# DAQ.net
KiCad netlist of a schematic drawn in Altium Designer
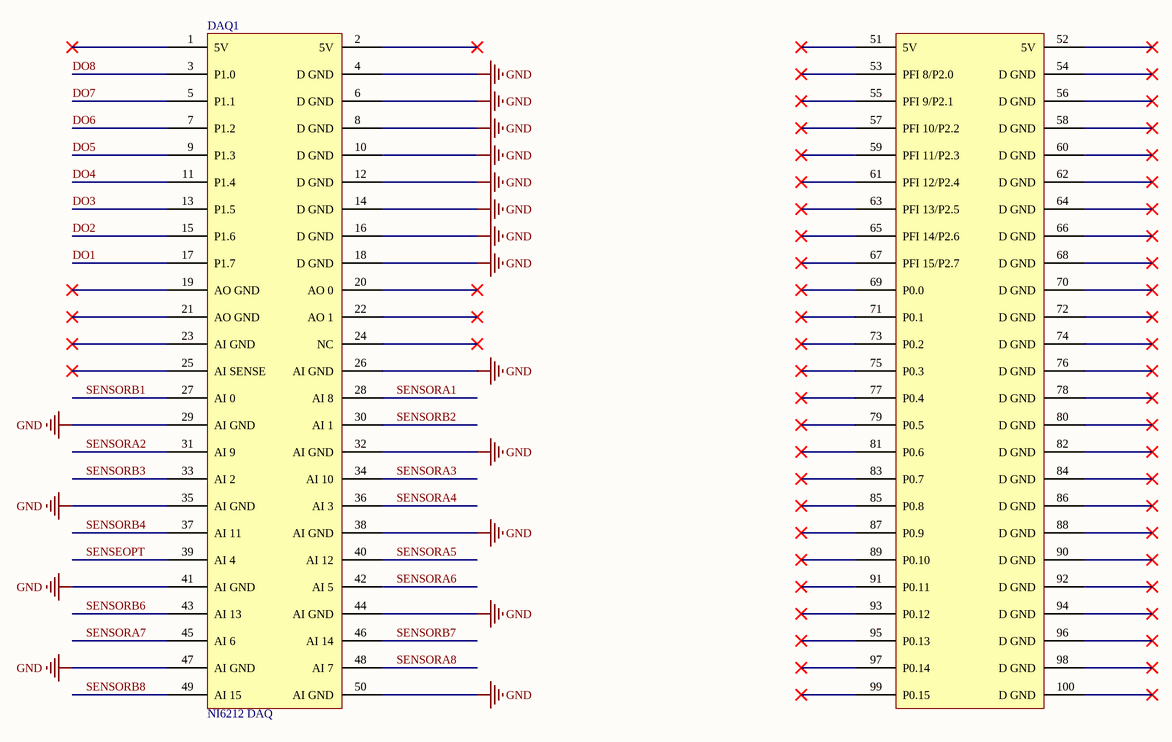
[diagram p0: DAQ.SchDoc]

(export (version "E")
  (design (tool "Eeschema 10.0.6"))
  (components
    (comp (ref "DAQ1")
      (value "NI6212 DAQ")
      (footprint "NIDAQ6212")
      (description "DAQ Unit")
      (fields (field (name "PUBLISHER") "National Instruments"))
      (libsource (lib "NI6212") (part "NI6212"))
    )
  )
  (nets
    (net (code "1") (name "/DO1") (class "Default")
      (node (ref "DAQ1") (pin "17") (pinfunction "P1.7_17") (pintype "passive"))
    )
    (net (code "2") (name "/DO2") (class "Default")
      (node (ref "DAQ1") (pin "15") (pinfunction "P1.6_15") (pintype "passive"))
    )
    (net (code "3") (name "/DO3") (class "Default")
      (node (ref "DAQ1") (pin "13") (pinfunction "P1.5_13") (pintype "passive"))
    )
    (net (code "4") (name "/DO4") (class "Default")
      (node (ref "DAQ1") (pin "11") (pinfunction "P1.4_11") (pintype "passive"))
    )
    (net (code "5") (name "/DO5") (class "Default")
      (node (ref "DAQ1") (pin "9") (pinfunction "P1.3_9") (pintype "passive"))
    )
    (net (code "6") (name "/DO6") (class "Default")
      (node (ref "DAQ1") (pin "7") (pinfunction "P1.2_7") (pintype "passive"))
    )
    (net (code "7") (name "/DO7") (class "Default")
      (node (ref "DAQ1") (pin "5") (pinfunction "P1.1_5") (pintype "passive"))
    )
    (net (code "8") (name "/DO8") (class "Default")
      (node (ref "DAQ1") (pin "3") (pinfunction "P1.0_3") (pintype "passive"))
    )
    (net (code "9") (name "/SENSEOPT") (class "Default")
      (node (ref "DAQ1") (pin "39") (pinfunction "AI_4_39") (pintype "passive"))
    )
    (net (code "10") (name "/SENSORA1") (class "Default")
      (node (ref "DAQ1") (pin "28") (pinfunction "AI_8_28") (pintype "passive"))
    )
    (net (code "11") (name "/SENSORA2") (class "Default")
      (node (ref "DAQ1") (pin "31") (pinfunction "AI_9_31") (pintype "passive"))
    )
    (net (code "12") (name "/SENSORA3") (class "Default")
      (node (ref "DAQ1") (pin "34") (pinfunction "AI_10_34") (pintype "passive"))
    )
    (net (code "13") (name "/SENSORA4") (class "Default")
      (node (ref "DAQ1") (pin "36") (pinfunction "AI_3_36") (pintype "passive"))
    )
    (net (code "14") (name "/SENSORA5") (class "Default")
      (node (ref "DAQ1") (pin "40") (pinfunction "AI_12_40") (pintype "passive"))
    )
    (net (code "15") (name "/SENSORA6") (class "Default")
      (node (ref "DAQ1") (pin "42") (pinfunction "AI_5_42") (pintype "passive"))
    )
    (net (code "16") (name "/SENSORA7") (class "Default")
      (node (ref "DAQ1") (pin "45") (pinfunction "AI_6_45") (pintype "passive"))
    )
    (net (code "17") (name "/SENSORA8") (class "Default")
      (node (ref "DAQ1") (pin "48") (pinfunction "AI_7_48") (pintype "passive"))
    )
    (net (code "18") (name "/SENSORB1") (class "Default")
      (node (ref "DAQ1") (pin "27") (pinfunction "AI_0_27") (pintype "passive"))
    )
    (net (code "19") (name "/SENSORB2") (class "Default")
      (node (ref "DAQ1") (pin "30") (pinfunction "AI_1_30") (pintype "passive"))
    )
    (net (code "20") (name "/SENSORB3") (class "Default")
      (node (ref "DAQ1") (pin "33") (pinfunction "AI_2_33") (pintype "passive"))
    )
    (net (code "21") (name "/SENSORB4") (class "Default")
      (node (ref "DAQ1") (pin "37") (pinfunction "AI_11_37") (pintype "passive"))
    )
    (net (code "22") (name "/SENSORB6") (class "Default")
      (node (ref "DAQ1") (pin "43") (pinfunction "AI_13_43") (pintype "passive"))
    )
    (net (code "23") (name "/SENSORB7") (class "Default")
      (node (ref "DAQ1") (pin "46") (pinfunction "AI_14_46") (pintype "passive"))
    )
    (net (code "24") (name "/SENSORB8") (class "Default")
      (node (ref "DAQ1") (pin "49") (pinfunction "AI_15_49") (pintype "passive"))
    )
    (net (code "25") (name "GND") (class "Default")
      (node (ref "DAQ1") (pin "10") (pinfunction "D_GND_10") (pintype "passive"))
      (node (ref "DAQ1") (pin "12") (pinfunction "D_GND_12") (pintype "passive"))
      (node (ref "DAQ1") (pin "14") (pinfunction "D_GND_14") (pintype "passive"))
      (node (ref "DAQ1") (pin "16") (pinfunction "D_GND_16") (pintype "passive"))
      (node (ref "DAQ1") (pin "18") (pinfunction "D_GND_18") (pintype "passive"))
      (node (ref "DAQ1") (pin "26") (pinfunction "AI_GND_26") (pintype "passive"))
      (node (ref "DAQ1") (pin "29") (pinfunction "AI_GND_29") (pintype "passive"))
      (node (ref "DAQ1") (pin "32") (pinfunction "AI_GND_32") (pintype "passive"))
      (node (ref "DAQ1") (pin "35") (pinfunction "AI_GND_35") (pintype "passive"))
      (node (ref "DAQ1") (pin "38") (pinfunction "AI_GND_38") (pintype "passive"))
      (node (ref "DAQ1") (pin "4") (pinfunction "D_GND_4") (pintype "passive"))
      (node (ref "DAQ1") (pin "41") (pinfunction "AI_GND_41") (pintype "passive"))
      (node (ref "DAQ1") (pin "44") (pinfunction "AI_GND_44") (pintype "passive"))
      (node (ref "DAQ1") (pin "47") (pinfunction "AI_GND_47") (pintype "passive"))
      (node (ref "DAQ1") (pin "50") (pinfunction "AI_GND_50") (pintype "passive"))
      (node (ref "DAQ1") (pin "6") (pinfunction "D_GND_6") (pintype "passive"))
      (node (ref "DAQ1") (pin "8") (pinfunction "D_GND_8") (pintype "passive"))
    )
    (net (code "26") (name "unconnected-(DAQ1-5V-Pad1)") (class "Default")
      (node (ref "DAQ1") (pin "1") (pinfunction "5V_1") (pintype "passive+no_connect"))
    )
    (net (code "27") (name "unconnected-(DAQ1-5V-Pad2)") (class "Default")
      (node (ref "DAQ1") (pin "2") (pinfunction "5V_2") (pintype "passive+no_connect"))
    )
    (net (code "28") (name "unconnected-(DAQ1-5V-Pad51)") (class "Default")
      (node (ref "DAQ1") (pin "51") (pinfunction "5V_51") (pintype "passive+no_connect"))
    )
    (net (code "29") (name "unconnected-(DAQ1-5V-Pad52)") (class "Default")
      (node (ref "DAQ1") (pin "52") (pinfunction "5V_52") (pintype "passive+no_connect"))
    )
    (net (code "30") (name "unconnected-(DAQ1-AI_GND-Pad23)") (class "Default")
      (node (ref "DAQ1") (pin "23") (pinfunction "AI_GND_23") (pintype "passive+no_connect"))
    )
    (net (code "31") (name "unconnected-(DAQ1-AI_SENSE-Pad25)") (class "Default")
      (node (ref "DAQ1") (pin "25") (pinfunction "AI_SENSE_25") (pintype "passive+no_connect"))
    )
    (net (code "32") (name "unconnected-(DAQ1-AO_0-Pad20)") (class "Default")
      (node (ref "DAQ1") (pin "20") (pinfunction "AO_0_20") (pintype "passive+no_connect"))
    )
    (net (code "33") (name "unconnected-(DAQ1-AO_1-Pad22)") (class "Default")
      (node (ref "DAQ1") (pin "22") (pinfunction "AO_1_22") (pintype "passive+no_connect"))
    )
    (net (code "34") (name "unconnected-(DAQ1-AO_GND-Pad19)") (class "Default")
      (node (ref "DAQ1") (pin "19") (pinfunction "AO_GND_19") (pintype "passive+no_connect"))
    )
    (net (code "35") (name "unconnected-(DAQ1-AO_GND-Pad21)") (class "Default")
      (node (ref "DAQ1") (pin "21") (pinfunction "AO_GND_21") (pintype "passive+no_connect"))
    )
    (net (code "36") (name "unconnected-(DAQ1-D_GND-Pad54)") (class "Default")
      (node (ref "DAQ1") (pin "54") (pinfunction "D_GND_54") (pintype "passive+no_connect"))
    )
    (net (code "37") (name "unconnected-(DAQ1-D_GND-Pad56)") (class "Default")
      (node (ref "DAQ1") (pin "56") (pinfunction "D_GND_56") (pintype "passive+no_connect"))
    )
    (net (code "38") (name "unconnected-(DAQ1-D_GND-Pad58)") (class "Default")
      (node (ref "DAQ1") (pin "58") (pinfunction "D_GND_58") (pintype "passive+no_connect"))
    )
    (net (code "39") (name "unconnected-(DAQ1-D_GND-Pad60)") (class "Default")
      (node (ref "DAQ1") (pin "60") (pinfunction "D_GND_60") (pintype "passive+no_connect"))
    )
    (net (code "40") (name "unconnected-(DAQ1-D_GND-Pad62)") (class "Default")
      (node (ref "DAQ1") (pin "62") (pinfunction "D_GND_62") (pintype "passive+no_connect"))
    )
    (net (code "41") (name "unconnected-(DAQ1-D_GND-Pad64)") (class "Default")
      (node (ref "DAQ1") (pin "64") (pinfunction "D_GND_64") (pintype "passive+no_connect"))
    )
    (net (code "42") (name "unconnected-(DAQ1-D_GND-Pad66)") (class "Default")
      (node (ref "DAQ1") (pin "66") (pinfunction "D_GND_66") (pintype "passive+no_connect"))
    )
    (net (code "43") (name "unconnected-(DAQ1-D_GND-Pad68)") (class "Default")
      (node (ref "DAQ1") (pin "68") (pinfunction "D_GND_68") (pintype "passive+no_connect"))
    )
    (net (code "44") (name "unconnected-(DAQ1-D_GND-Pad70)") (class "Default")
      (node (ref "DAQ1") (pin "70") (pinfunction "D_GND_70") (pintype "passive+no_connect"))
    )
    (net (code "45") (name "unconnected-(DAQ1-D_GND-Pad72)") (class "Default")
      (node (ref "DAQ1") (pin "72") (pinfunction "D_GND_72") (pintype "passive+no_connect"))
    )
    (net (code "46") (name "unconnected-(DAQ1-D_GND-Pad74)") (class "Default")
      (node (ref "DAQ1") (pin "74") (pinfunction "D_GND_74") (pintype "passive+no_connect"))
    )
    (net (code "47") (name "unconnected-(DAQ1-D_GND-Pad76)") (class "Default")
      (node (ref "DAQ1") (pin "76") (pinfunction "D_GND_76") (pintype "passive+no_connect"))
    )
    (net (code "48") (name "unconnected-(DAQ1-D_GND-Pad78)") (class "Default")
      (node (ref "DAQ1") (pin "78") (pinfunction "D_GND_78") (pintype "passive+no_connect"))
    )
    (net (code "49") (name "unconnected-(DAQ1-D_GND-Pad80)") (class "Default")
      (node (ref "DAQ1") (pin "80") (pinfunction "D_GND_80") (pintype "passive+no_connect"))
    )
    (net (code "50") (name "unconnected-(DAQ1-D_GND-Pad82)") (class "Default")
      (node (ref "DAQ1") (pin "82") (pinfunction "D_GND_82") (pintype "passive+no_connect"))
    )
    (net (code "51") (name "unconnected-(DAQ1-D_GND-Pad84)") (class "Default")
      (node (ref "DAQ1") (pin "84") (pinfunction "D_GND_84") (pintype "passive+no_connect"))
    )
    (net (code "52") (name "unconnected-(DAQ1-D_GND-Pad86)") (class "Default")
      (node (ref "DAQ1") (pin "86") (pinfunction "D_GND_86") (pintype "passive+no_connect"))
    )
    (net (code "53") (name "unconnected-(DAQ1-D_GND-Pad88)") (class "Default")
      (node (ref "DAQ1") (pin "88") (pinfunction "D_GND_88") (pintype "passive+no_connect"))
    )
    (net (code "54") (name "unconnected-(DAQ1-D_GND-Pad90)") (class "Default")
      (node (ref "DAQ1") (pin "90") (pinfunction "D_GND_90") (pintype "passive+no_connect"))
    )
    (net (code "55") (name "unconnected-(DAQ1-D_GND-Pad92)") (class "Default")
      (node (ref "DAQ1") (pin "92") (pinfunction "D_GND_92") (pintype "passive+no_connect"))
    )
    (net (code "56") (name "unconnected-(DAQ1-D_GND-Pad94)") (class "Default")
      (node (ref "DAQ1") (pin "94") (pinfunction "D_GND_94") (pintype "passive+no_connect"))
    )
    (net (code "57") (name "unconnected-(DAQ1-D_GND-Pad96)") (class "Default")
      (node (ref "DAQ1") (pin "96") (pinfunction "D_GND_96") (pintype "passive+no_connect"))
    )
    (net (code "58") (name "unconnected-(DAQ1-D_GND-Pad98)") (class "Default")
      (node (ref "DAQ1") (pin "98") (pinfunction "D_GND_98") (pintype "passive+no_connect"))
    )
    (net (code "59") (name "unconnected-(DAQ1-D_GND-Pad100)") (class "Default")
      (node (ref "DAQ1") (pin "100") (pinfunction "D_GND_100") (pintype "passive+no_connect"))
    )
    (net (code "60") (name "unconnected-(DAQ1-NC-Pad24)") (class "Default")
      (node (ref "DAQ1") (pin "24") (pinfunction "NC_24") (pintype "passive+no_connect"))
    )
    (net (code "61") (name "unconnected-(DAQ1-P0.0-Pad69)") (class "Default")
      (node (ref "DAQ1") (pin "69") (pinfunction "P0.0_69") (pintype "passive+no_connect"))
    )
    (net (code "62") (name "unconnected-(DAQ1-P0.1-Pad71)") (class "Default")
      (node (ref "DAQ1") (pin "71") (pinfunction "P0.1_71") (pintype "passive+no_connect"))
    )
    (net (code "63") (name "unconnected-(DAQ1-P0.2-Pad73)") (class "Default")
      (node (ref "DAQ1") (pin "73") (pinfunction "P0.2_73") (pintype "passive+no_connect"))
    )
    (net (code "64") (name "unconnected-(DAQ1-P0.3-Pad75)") (class "Default")
      (node (ref "DAQ1") (pin "75") (pinfunction "P0.3_75") (pintype "passive+no_connect"))
    )
    (net (code "65") (name "unconnected-(DAQ1-P0.4-Pad77)") (class "Default")
      (node (ref "DAQ1") (pin "77") (pinfunction "P0.4_77") (pintype "passive+no_connect"))
    )
    (net (code "66") (name "unconnected-(DAQ1-P0.5-Pad79)") (class "Default")
      (node (ref "DAQ1") (pin "79") (pinfunction "P0.5_79") (pintype "passive+no_connect"))
    )
    (net (code "67") (name "unconnected-(DAQ1-P0.6-Pad81)") (class "Default")
      (node (ref "DAQ1") (pin "81") (pinfunction "P0.6_81") (pintype "passive+no_connect"))
    )
    (net (code "68") (name "unconnected-(DAQ1-P0.7-Pad83)") (class "Default")
      (node (ref "DAQ1") (pin "83") (pinfunction "P0.7_83") (pintype "passive+no_connect"))
    )
    (net (code "69") (name "unconnected-(DAQ1-P0.8-Pad85)") (class "Default")
      (node (ref "DAQ1") (pin "85") (pinfunction "P0.8_85") (pintype "passive+no_connect"))
    )
    (net (code "70") (name "unconnected-(DAQ1-P0.9-Pad87)") (class "Default")
      (node (ref "DAQ1") (pin "87") (pinfunction "P0.9_87") (pintype "passive+no_connect"))
    )
    (net (code "71") (name "unconnected-(DAQ1-P0.10-Pad89)") (class "Default")
      (node (ref "DAQ1") (pin "89") (pinfunction "P0.10_89") (pintype "passive+no_connect"))
    )
    (net (code "72") (name "unconnected-(DAQ1-P0.11-Pad91)") (class "Default")
      (node (ref "DAQ1") (pin "91") (pinfunction "P0.11_91") (pintype "passive+no_connect"))
    )
    (net (code "73") (name "unconnected-(DAQ1-P0.12-Pad93)") (class "Default")
      (node (ref "DAQ1") (pin "93") (pinfunction "P0.12_93") (pintype "passive+no_connect"))
    )
    (net (code "74") (name "unconnected-(DAQ1-P0.13-Pad95)") (class "Default")
      (node (ref "DAQ1") (pin "95") (pinfunction "P0.13_95") (pintype "passive+no_connect"))
    )
    (net (code "75") (name "unconnected-(DAQ1-P0.14-Pad97)") (class "Default")
      (node (ref "DAQ1") (pin "97") (pinfunction "P0.14_97") (pintype "passive+no_connect"))
    )
    (net (code "76") (name "unconnected-(DAQ1-P0.15-Pad99)") (class "Default")
      (node (ref "DAQ1") (pin "99") (pinfunction "P0.15_99") (pintype "passive+no_connect"))
    )
    (net (code "77") (name "unconnected-(DAQ1-PFI_8{slash}P2.0-Pad53)") (class "Default")
      (node (ref "DAQ1") (pin "53") (pinfunction "PFI_8/P2.0_53") (pintype "passive+no_connect"))
    )
    (net (code "78") (name "unconnected-(DAQ1-PFI_9{slash}P2.1-Pad55)") (class "Default")
      (node (ref "DAQ1") (pin "55") (pinfunction "PFI_9/P2.1_55") (pintype "passive+no_connect"))
    )
    (net (code "79") (name "unconnected-(DAQ1-PFI_10{slash}P2.2-Pad57)") (class "Default")
      (node (ref "DAQ1") (pin "57") (pinfunction "PFI_10/P2.2_57") (pintype "passive+no_connect"))
    )
    (net (code "80") (name "unconnected-(DAQ1-PFI_11{slash}P2.3-Pad59)") (class "Default")
      (node (ref "DAQ1") (pin "59") (pinfunction "PFI_11/P2.3_59") (pintype "passive+no_connect"))
    )
    (net (code "81") (name "unconnected-(DAQ1-PFI_12{slash}P2.4-Pad61)") (class "Default")
      (node (ref "DAQ1") (pin "61") (pinfunction "PFI_12/P2.4_61") (pintype "passive+no_connect"))
    )
    (net (code "82") (name "unconnected-(DAQ1-PFI_13{slash}P2.5-Pad63)") (class "Default")
      (node (ref "DAQ1") (pin "63") (pinfunction "PFI_13/P2.5_63") (pintype "passive+no_connect"))
    )
    (net (code "83") (name "unconnected-(DAQ1-PFI_14{slash}P2.6-Pad65)") (class "Default")
      (node (ref "DAQ1") (pin "65") (pinfunction "PFI_14/P2.6_65") (pintype "passive+no_connect"))
    )
    (net (code "84") (name "unconnected-(DAQ1-PFI_15{slash}P2.7-Pad67)") (class "Default")
      (node (ref "DAQ1") (pin "67") (pinfunction "PFI_15/P2.7_67") (pintype "passive+no_connect"))
    )
  )
)
